# 02_IO.net
KiCad netlist of a schematic drawn in Altium Designer
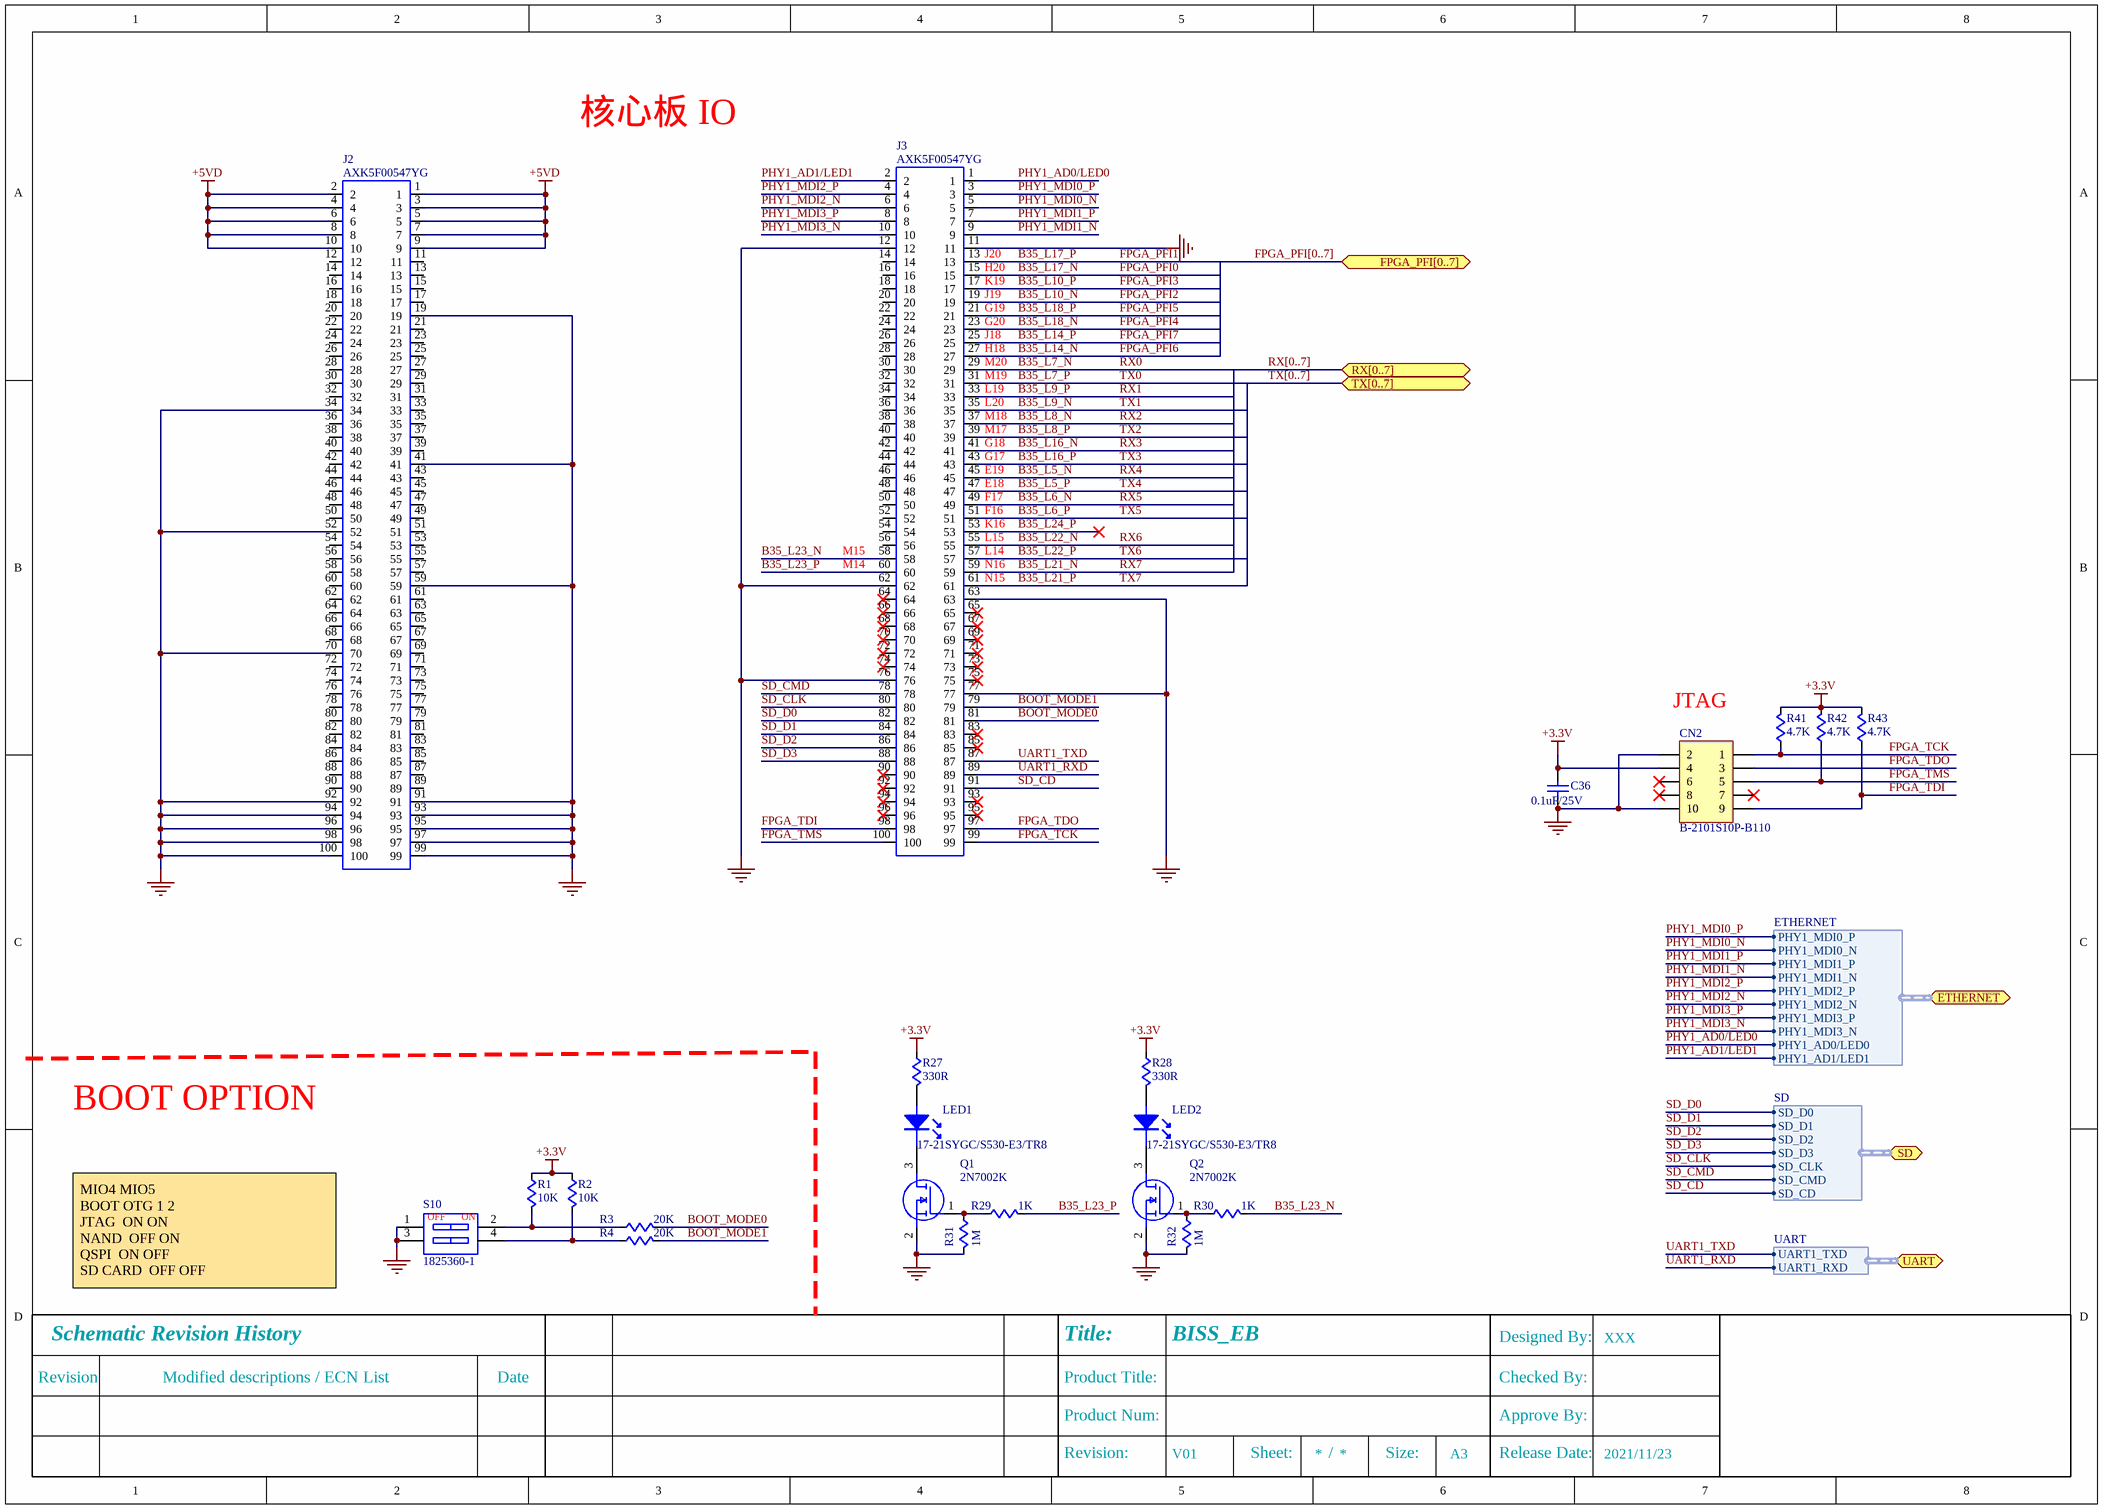
[diagram p0: 02_IO.SchDoc]

(export (version "E")
  (design (tool "Eeschema 10.0.6"))
  (components
    (comp (ref "C36")
      (value "0.1uF/25V")
      (footprint "SamacSys:C0603")
      (description "MLCC")
      (libsource (lib "SamacSys") (part "C"))
    )
    (comp (ref "CN2")
      (value "B-2101S10P-B110")
      (footprint "SHF10501FDTH")
      (description "5*2P接插件,间距1.27mm,参考链接：https://so.szlcsc.com/global.html?k=B-2101S10P-B110&hot-key=LM358")
      (fields (field (name "版权归属") "源创客"))
      (libsource (lib "4.3   - 接插件-脚距1.27") (part "Header 5X2"))
    )
    (comp (ref "J2")
      (value "AXK5F00547YG")
      (footprint "AXK5F00547YG")
      (description "Header_2X50_0.5mm")
      (libsource (lib "*") (part "Header_2X50"))
    )
    (comp (ref "J3")
      (value "AXK5F00547YG")
      (footprint "AXK5F00547YG")
      (description "Header_2X50_0.5mm")
      (libsource (lib "*") (part "Header_2X50"))
    )
    (comp (ref "LED1")
      (value "17-21SYGC/S530-E3/TR8")
      (footprint "LED_0805")
      (libsource (lib "Topband1") (part "LED"))
    )
    (comp (ref "LED2")
      (value "17-21SYGC/S530-E3/TR8")
      (footprint "LED_0805")
      (libsource (lib "Topband1") (part "LED"))
    )
    (comp (ref "Q1")
      (value "2N7002K")
      (footprint "SamacSys:SOT95P240X120-3N")
      (description "MOSFET (N-Channel)")
      (fields (field (name "MOUSER PART NUMBER") "512-2N7002K"))
      (libsource (lib "*") (part "2N7002K"))
    )
    (comp (ref "Q2")
      (value "2N7002K")
      (footprint "SamacSys:SOT95P240X120-3N")
      (description "MOSFET (N-Channel)")
      (fields (field (name "MOUSER PART NUMBER") "512-2N7002K"))
      (libsource (lib "*") (part "2N7002K"))
    )
    (comp (ref "R1")
      (value "10K")
      (footprint "SamacSys:R0603")
      (description "贴片电阻")
      (libsource (lib "SamacSys") (part "R"))
    )
    (comp (ref "R2")
      (value "10K")
      (footprint "SamacSys:R0603")
      (description "贴片电阻")
      (libsource (lib "SamacSys") (part "R"))
    )
    (comp (ref "R3")
      (value "20K")
      (footprint "SamacSys:R0603")
      (description "贴片电阻")
      (libsource (lib "SamacSys") (part "R"))
    )
    (comp (ref "R4")
      (value "20K")
      (footprint "SamacSys:R0603")
      (description "贴片电阻")
      (libsource (lib "SamacSys") (part "R"))
    )
    (comp (ref "R27")
      (value "330R")
      (footprint "SamacSys:R0603")
      (description "贴片电阻")
      (libsource (lib "SamacSys") (part "R"))
    )
    (comp (ref "R28")
      (value "330R")
      (footprint "SamacSys:R0603")
      (description "贴片电阻")
      (libsource (lib "SamacSys") (part "R"))
    )
    (comp (ref "R29")
      (value "1K")
      (footprint "SamacSys:R0603")
      (description "贴片电阻")
      (libsource (lib "SamacSys") (part "R"))
    )
    (comp (ref "R30")
      (value "1K")
      (footprint "SamacSys:R0603")
      (description "贴片电阻")
      (libsource (lib "SamacSys") (part "R"))
    )
    (comp (ref "R31")
      (value "1M")
      (footprint "SamacSys:R0603")
      (description "贴片电阻")
      (libsource (lib "SamacSys") (part "R"))
    )
    (comp (ref "R32")
      (value "1M")
      (footprint "SamacSys:R0603")
      (description "贴片电阻")
      (libsource (lib "SamacSys") (part "R"))
    )
    (comp (ref "R41")
      (value "4.7K")
      (footprint "SamacSys:R0603")
      (description "贴片电阻")
      (libsource (lib "SamacSys") (part "R"))
    )
    (comp (ref "R42")
      (value "4.7K")
      (footprint "SamacSys:R0603")
      (description "贴片电阻")
      (libsource (lib "SamacSys") (part "R"))
    )
    (comp (ref "R43")
      (value "4.7K")
      (footprint "SamacSys:R0603")
      (description "贴片电阻")
      (libsource (lib "SamacSys") (part "R"))
    )
    (comp (ref "S10")
      (value "1825360-1")
      (footprint "SamacSys:18253601")
      (description "Switch")
      (fields (field (name "MOUSER PART NUMBER") "655-1825360-1"))
      (libsource (lib "SamacSys") (part "1825360-1"))
    )
  )
  (nets
    (net (code "4") (name "+3.3V") (class "Default")
      (node (ref "C36") (pin "1") (pinfunction "1_1") (pintype "passive"))
      (node (ref "CN2") (pin "4") (pinfunction "4_4") (pintype "passive"))
      (node (ref "R1") (pin "1") (pinfunction "1_1") (pintype "passive"))
      (node (ref "R2") (pin "1") (pinfunction "1_1") (pintype "passive"))
      (node (ref "R27") (pin "1") (pinfunction "1_1") (pintype "passive"))
      (node (ref "R28") (pin "1") (pinfunction "1_1") (pintype "passive"))
      (node (ref "R41") (pin "2") (pinfunction "2_2") (pintype "passive"))
      (node (ref "R42") (pin "2") (pinfunction "2_2") (pintype "passive"))
      (node (ref "R43") (pin "2") (pinfunction "2_2") (pintype "passive"))
    )
    (net (code "5") (name "+5VD") (class "Default")
      (node (ref "J2") (pin "1") (pinfunction "1_1") (pintype "passive"))
      (node (ref "J2") (pin "10") (pinfunction "10_10") (pintype "passive"))
      (node (ref "J2") (pin "2") (pinfunction "2_2") (pintype "passive"))
      (node (ref "J2") (pin "3") (pinfunction "3_3") (pintype "passive"))
      (node (ref "J2") (pin "4") (pinfunction "4_4") (pintype "passive"))
      (node (ref "J2") (pin "5") (pinfunction "5_5") (pintype "passive"))
      (node (ref "J2") (pin "6") (pinfunction "6_6") (pintype "passive"))
      (node (ref "J2") (pin "7") (pinfunction "7_7") (pintype "passive"))
      (node (ref "J2") (pin "8") (pinfunction "8_8") (pintype "passive"))
      (node (ref "J2") (pin "9") (pinfunction "9_9") (pintype "passive"))
    )
    (net (code "6") (name "/B35_L23_N") (class "Default")
      (node (ref "J3") (pin "58") (pinfunction "58_58") (pintype "passive"))
      (node (ref "R30") (pin "2") (pinfunction "2_2") (pintype "passive"))
    )
    (net (code "7") (name "/B35_L23_P") (class "Default")
      (node (ref "J3") (pin "60") (pinfunction "60_60") (pintype "passive"))
      (node (ref "R29") (pin "2") (pinfunction "2_2") (pintype "passive"))
    )
    (net (code "8") (name "/B35_L24_P") (class "Default")
      (node (ref "J3") (pin "53") (pinfunction "53_53") (pintype "passive+no_connect"))
    )
    (net (code "9") (name "/BOOT_MODE0") (class "Default")
      (node (ref "J3") (pin "81") (pinfunction "81_81") (pintype "passive"))
      (node (ref "R3") (pin "2") (pinfunction "2_2") (pintype "passive"))
    )
    (net (code "10") (name "/BOOT_MODE1") (class "Default")
      (node (ref "J3") (pin "79") (pinfunction "79_79") (pintype "passive"))
      (node (ref "R4") (pin "2") (pinfunction "2_2") (pintype "passive"))
    )
    (net (code "11") (name "/FPGA_PFI0") (class "Default")
      (node (ref "J3") (pin "15") (pinfunction "15_15") (pintype "passive"))
    )
    (net (code "12") (name "/FPGA_PFI1") (class "Default")
      (node (ref "J3") (pin "13") (pinfunction "13_13") (pintype "passive"))
    )
    (net (code "13") (name "/FPGA_PFI2") (class "Default")
      (node (ref "J3") (pin "19") (pinfunction "19_19") (pintype "passive"))
    )
    (net (code "14") (name "/FPGA_PFI3") (class "Default")
      (node (ref "J3") (pin "17") (pinfunction "17_17") (pintype "passive"))
    )
    (net (code "15") (name "/FPGA_PFI4") (class "Default")
      (node (ref "J3") (pin "23") (pinfunction "23_23") (pintype "passive"))
    )
    (net (code "16") (name "/FPGA_PFI5") (class "Default")
      (node (ref "J3") (pin "21") (pinfunction "21_21") (pintype "passive"))
    )
    (net (code "17") (name "/FPGA_PFI6") (class "Default")
      (node (ref "J3") (pin "27") (pinfunction "27_27") (pintype "passive"))
    )
    (net (code "18") (name "/FPGA_PFI7") (class "Default")
      (node (ref "J3") (pin "25") (pinfunction "25_25") (pintype "passive"))
    )
    (net (code "20") (name "/FPGA_TCK") (class "Default")
      (node (ref "CN2") (pin "1") (pinfunction "1_1") (pintype "passive"))
      (node (ref "J3") (pin "99") (pinfunction "99_99") (pintype "passive"))
      (node (ref "R41") (pin "1") (pinfunction "1_1") (pintype "passive"))
    )
    (net (code "21") (name "/FPGA_TDI") (class "Default")
      (node (ref "CN2") (pin "9") (pinfunction "9_9") (pintype "passive"))
      (node (ref "J3") (pin "98") (pinfunction "98_98") (pintype "passive"))
      (node (ref "R43") (pin "1") (pinfunction "1_1") (pintype "passive"))
    )
    (net (code "22") (name "/FPGA_TDO") (class "Default")
      (node (ref "CN2") (pin "3") (pinfunction "3_3") (pintype "passive"))
      (node (ref "J3") (pin "97") (pinfunction "97_97") (pintype "passive"))
    )
    (net (code "23") (name "/FPGA_TMS") (class "Default")
      (node (ref "CN2") (pin "5") (pinfunction "5_5") (pintype "passive"))
      (node (ref "J3") (pin "100") (pinfunction "100_100") (pintype "passive"))
      (node (ref "R42") (pin "1") (pinfunction "1_1") (pintype "passive"))
    )
    (net (code "24") (name "/PHY1_AD0{slash}LED0") (class "Default")
      (node (ref "J3") (pin "1") (pinfunction "1_1") (pintype "passive"))
    )
    (net (code "25") (name "/PHY1_AD1{slash}LED1") (class "Default")
      (node (ref "J3") (pin "2") (pinfunction "2_2") (pintype "passive"))
    )
    (net (code "26") (name "/PHY1_MDI0_N") (class "Default")
      (node (ref "J3") (pin "5") (pinfunction "5_5") (pintype "passive"))
    )
    (net (code "27") (name "/PHY1_MDI0_P") (class "Default")
      (node (ref "J3") (pin "3") (pinfunction "3_3") (pintype "passive"))
    )
    (net (code "28") (name "/PHY1_MDI1_N") (class "Default")
      (node (ref "J3") (pin "9") (pinfunction "9_9") (pintype "passive"))
    )
    (net (code "29") (name "/PHY1_MDI1_P") (class "Default")
      (node (ref "J3") (pin "7") (pinfunction "7_7") (pintype "passive"))
    )
    (net (code "30") (name "/PHY1_MDI2_N") (class "Default")
      (node (ref "J3") (pin "6") (pinfunction "6_6") (pintype "passive"))
    )
    (net (code "31") (name "/PHY1_MDI2_P") (class "Default")
      (node (ref "J3") (pin "4") (pinfunction "4_4") (pintype "passive"))
    )
    (net (code "32") (name "/PHY1_MDI3_N") (class "Default")
      (node (ref "J3") (pin "10") (pinfunction "10_10") (pintype "passive"))
    )
    (net (code "33") (name "/PHY1_MDI3_P") (class "Default")
      (node (ref "J3") (pin "8") (pinfunction "8_8") (pintype "passive"))
    )
    (net (code "34") (name "/RX0") (class "Default")
      (node (ref "J3") (pin "29") (pinfunction "29_29") (pintype "passive"))
    )
    (net (code "35") (name "/RX1") (class "Default")
      (node (ref "J3") (pin "33") (pinfunction "33_33") (pintype "passive"))
    )
    (net (code "36") (name "/RX2") (class "Default")
      (node (ref "J3") (pin "37") (pinfunction "37_37") (pintype "passive"))
    )
    (net (code "37") (name "/RX3") (class "Default")
      (node (ref "J3") (pin "41") (pinfunction "41_41") (pintype "passive"))
    )
    (net (code "38") (name "/RX4") (class "Default")
      (node (ref "J3") (pin "45") (pinfunction "45_45") (pintype "passive"))
    )
    (net (code "39") (name "/RX5") (class "Default")
      (node (ref "J3") (pin "49") (pinfunction "49_49") (pintype "passive"))
    )
    (net (code "40") (name "/RX6") (class "Default")
      (node (ref "J3") (pin "55") (pinfunction "55_55") (pintype "passive"))
    )
    (net (code "41") (name "/RX7") (class "Default")
      (node (ref "J3") (pin "59") (pinfunction "59_59") (pintype "passive"))
    )
    (net (code "43") (name "/SD_CD") (class "Default")
      (node (ref "J3") (pin "91") (pinfunction "91_91") (pintype "passive"))
    )
    (net (code "44") (name "/SD_CLK") (class "Default")
      (node (ref "J3") (pin "80") (pinfunction "80_80") (pintype "passive"))
    )
    (net (code "45") (name "/SD_CMD") (class "Default")
      (node (ref "J3") (pin "78") (pinfunction "78_78") (pintype "passive"))
    )
    (net (code "46") (name "/SD_D0") (class "Default")
      (node (ref "J3") (pin "82") (pinfunction "82_82") (pintype "passive"))
    )
    (net (code "47") (name "/SD_D1") (class "Default")
      (node (ref "J3") (pin "84") (pinfunction "84_84") (pintype "passive"))
    )
    (net (code "48") (name "/SD_D2") (class "Default")
      (node (ref "J3") (pin "86") (pinfunction "86_86") (pintype "passive"))
    )
    (net (code "49") (name "/SD_D3") (class "Default")
      (node (ref "J3") (pin "88") (pinfunction "88_88") (pintype "passive"))
    )
    (net (code "50") (name "/TX0") (class "Default")
      (node (ref "J3") (pin "31") (pinfunction "31_31") (pintype "passive"))
    )
    (net (code "51") (name "/TX1") (class "Default")
      (node (ref "J3") (pin "35") (pinfunction "35_35") (pintype "passive"))
    )
    (net (code "52") (name "/TX2") (class "Default")
      (node (ref "J3") (pin "39") (pinfunction "39_39") (pintype "passive"))
    )
    (net (code "53") (name "/TX3") (class "Default")
      (node (ref "J3") (pin "43") (pinfunction "43_43") (pintype "passive"))
    )
    (net (code "54") (name "/TX4") (class "Default")
      (node (ref "J3") (pin "47") (pinfunction "47_47") (pintype "passive"))
    )
    (net (code "55") (name "/TX5") (class "Default")
      (node (ref "J3") (pin "51") (pinfunction "51_51") (pintype "passive"))
    )
    (net (code "56") (name "/TX6") (class "Default")
      (node (ref "J3") (pin "57") (pinfunction "57_57") (pintype "passive"))
    )
    (net (code "57") (name "/TX7") (class "Default")
      (node (ref "J3") (pin "61") (pinfunction "61_61") (pintype "passive"))
    )
    (net (code "59") (name "/UART1_RXD") (class "Default")
      (node (ref "J3") (pin "89") (pinfunction "89_89") (pintype "passive"))
    )
    (net (code "60") (name "/UART1_TXD") (class "Default")
      (node (ref "J3") (pin "87") (pinfunction "87_87") (pintype "passive"))
    )
    (net (code "64") (name "GND") (class "Default")
      (node (ref "C36") (pin "2") (pinfunction "2_2") (pintype "passive"))
      (node (ref "CN2") (pin "10") (pinfunction "10_10") (pintype "passive"))
      (node (ref "CN2") (pin "2") (pinfunction "2_2") (pintype "passive"))
      (node (ref "J2") (pin "100") (pinfunction "100_100") (pintype "passive"))
      (node (ref "J2") (pin "19") (pinfunction "19_19") (pintype "passive"))
      (node (ref "J2") (pin "34") (pinfunction "34_34") (pintype "passive"))
      (node (ref "J2") (pin "41") (pinfunction "41_41") (pintype "passive"))
      (node (ref "J2") (pin "52") (pinfunction "52_52") (pintype "passive"))
      (node (ref "J2") (pin "59") (pinfunction "59_59") (pintype "passive"))
      (node (ref "J2") (pin "70") (pinfunction "70_70") (pintype "passive"))
      (node (ref "J2") (pin "91") (pinfunction "91_91") (pintype "passive"))
      (node (ref "J2") (pin "92") (pinfunction "92_92") (pintype "passive"))
      (node (ref "J2") (pin "93") (pinfunction "93_93") (pintype "passive"))
      (node (ref "J2") (pin "94") (pinfunction "94_94") (pintype "passive"))
      (node (ref "J2") (pin "95") (pinfunction "95_95") (pintype "passive"))
      (node (ref "J2") (pin "96") (pinfunction "96_96") (pintype "passive"))
      (node (ref "J2") (pin "97") (pinfunction "97_97") (pintype "passive"))
      (node (ref "J2") (pin "98") (pinfunction "98_98") (pintype "passive"))
      (node (ref "J2") (pin "99") (pinfunction "99_99") (pintype "passive"))
      (node (ref "J3") (pin "11") (pinfunction "11_11") (pintype "passive"))
      (node (ref "J3") (pin "12") (pinfunction "12_12") (pintype "passive"))
      (node (ref "J3") (pin "62") (pinfunction "62_62") (pintype "passive"))
      (node (ref "J3") (pin "63") (pinfunction "63_63") (pintype "passive"))
      (node (ref "J3") (pin "76") (pinfunction "76_76") (pintype "passive"))
      (node (ref "J3") (pin "77") (pinfunction "77_77") (pintype "passive"))
      (node (ref "Q1") (pin "2") (pinfunction "S_2") (pintype "passive"))
      (node (ref "Q2") (pin "2") (pinfunction "S_2") (pintype "passive"))
      (node (ref "R31") (pin "2") (pinfunction "2_2") (pintype "passive"))
      (node (ref "R32") (pin "2") (pinfunction "2_2") (pintype "passive"))
      (node (ref "S10") (pin "1") (pinfunction "1_1") (pintype "passive"))
      (node (ref "S10") (pin "3") (pinfunction "3_3") (pintype "passive"))
    )
    (net (code "65") (name "Net-(LED1-PadA)") (class "Default")
      (node (ref "LED1") (pin "A") (pinfunction "A_A") (pintype "passive"))
      (node (ref "R27") (pin "2") (pinfunction "2_2") (pintype "passive"))
    )
    (net (code "66") (name "Net-(LED2-PadA)") (class "Default")
      (node (ref "LED2") (pin "A") (pinfunction "A_A") (pintype "passive"))
      (node (ref "R28") (pin "2") (pinfunction "2_2") (pintype "passive"))
    )
    (net (code "67") (name "Net-(Q1-D)") (class "Default")
      (node (ref "LED1") (pin "K") (pinfunction "K_K") (pintype "passive"))
      (node (ref "Q1") (pin "3") (pinfunction "D_3") (pintype "passive"))
    )
    (net (code "68") (name "Net-(Q1-G)") (class "Default")
      (node (ref "Q1") (pin "1") (pinfunction "G_1") (pintype "passive"))
      (node (ref "R29") (pin "1") (pinfunction "1_1") (pintype "passive"))
      (node (ref "R31") (pin "1") (pinfunction "1_1") (pintype "passive"))
    )
    (net (code "69") (name "Net-(Q2-D)") (class "Default")
      (node (ref "LED2") (pin "K") (pinfunction "K_K") (pintype "passive"))
      (node (ref "Q2") (pin "3") (pinfunction "D_3") (pintype "passive"))
    )
    (net (code "70") (name "Net-(Q2-G)") (class "Default")
      (node (ref "Q2") (pin "1") (pinfunction "G_1") (pintype "passive"))
      (node (ref "R30") (pin "1") (pinfunction "1_1") (pintype "passive"))
      (node (ref "R32") (pin "1") (pinfunction "1_1") (pintype "passive"))
    )
    (net (code "71") (name "Net-(R1-Pad2)") (class "Default")
      (node (ref "R1") (pin "2") (pinfunction "2_2") (pintype "passive"))
      (node (ref "R3") (pin "1") (pinfunction "1_1") (pintype "passive"))
      (node (ref "S10") (pin "2") (pinfunction "2_2") (pintype "passive"))
    )
    (net (code "72") (name "Net-(R2-Pad2)") (class "Default")
      (node (ref "R2") (pin "2") (pinfunction "2_2") (pintype "passive"))
      (node (ref "R4") (pin "1") (pinfunction "1_1") (pintype "passive"))
      (node (ref "S10") (pin "4") (pinfunction "4_4") (pintype "passive"))
    )
    (net (code "73") (name "unconnected-(CN2-Pad6)") (class "Default")
      (node (ref "CN2") (pin "6") (pinfunction "6_6") (pintype "passive+no_connect"))
    )
    (net (code "74") (name "unconnected-(CN2-Pad7)") (class "Default")
      (node (ref "CN2") (pin "7") (pinfunction "7_7") (pintype "passive+no_connect"))
    )
    (net (code "75") (name "unconnected-(CN2-Pad8)") (class "Default")
      (node (ref "CN2") (pin "8") (pinfunction "8_8") (pintype "passive+no_connect"))
    )
    (net (code "76") (name "unconnected-(J2-Pad11)") (class "Default")
      (node (ref "J2") (pin "11") (pinfunction "11_11") (pintype "passive"))
    )
    (net (code "77") (name "unconnected-(J2-Pad12)") (class "Default")
      (node (ref "J2") (pin "12") (pinfunction "12_12") (pintype "passive"))
    )
    (net (code "78") (name "unconnected-(J2-Pad13)") (class "Default")
      (node (ref "J2") (pin "13") (pinfunction "13_13") (pintype "passive"))
    )
    (net (code "79") (name "unconnected-(J2-Pad14)") (class "Default")
      (node (ref "J2") (pin "14") (pinfunction "14_14") (pintype "passive"))
    )
    (net (code "80") (name "unconnected-(J2-Pad15)") (class "Default")
      (node (ref "J2") (pin "15") (pinfunction "15_15") (pintype "passive"))
    )
    (net (code "81") (name "unconnected-(J2-Pad16)") (class "Default")
      (node (ref "J2") (pin "16") (pinfunction "16_16") (pintype "passive"))
    )
    (net (code "82") (name "unconnected-(J2-Pad17)") (class "Default")
      (node (ref "J2") (pin "17") (pinfunction "17_17") (pintype "passive"))
    )
    (net (code "83") (name "unconnected-(J2-Pad18)") (class "Default")
      (node (ref "J2") (pin "18") (pinfunction "18_18") (pintype "passive"))
    )
    (net (code "84") (name "unconnected-(J2-Pad20)") (class "Default")
      (node (ref "J2") (pin "20") (pinfunction "20_20") (pintype "passive"))
    )
    (net (code "85") (name "unconnected-(J2-Pad21)") (class "Default")
      (node (ref "J2") (pin "21") (pinfunction "21_21") (pintype "passive"))
    )
    (net (code "86") (name "unconnected-(J2-Pad22)") (class "Default")
      (node (ref "J2") (pin "22") (pinfunction "22_22") (pintype "passive"))
    )
    (net (code "87") (name "unconnected-(J2-Pad23)") (class "Default")
      (node (ref "J2") (pin "23") (pinfunction "23_23") (pintype "passive"))
    )
    (net (code "88") (name "unconnected-(J2-Pad24)") (class "Default")
      (node (ref "J2") (pin "24") (pinfunction "24_24") (pintype "passive"))
    )
    (net (code "89") (name "unconnected-(J2-Pad25)") (class "Default")
      (node (ref "J2") (pin "25") (pinfunction "25_25") (pintype "passive"))
    )
    (net (code "90") (name "unconnected-(J2-Pad26)") (class "Default")
      (node (ref "J2") (pin "26") (pinfunction "26_26") (pintype "passive"))
    )
    (net (code "91") (name "unconnected-(J2-Pad27)") (class "Default")
      (node (ref "J2") (pin "27") (pinfunction "27_27") (pintype "passive"))
    )
    (net (code "92") (name "unconnected-(J2-Pad28)") (class "Default")
      (node (ref "J2") (pin "28") (pinfunction "28_28") (pintype "passive"))
    )
    (net (code "93") (name "unconnected-(J2-Pad29)") (class "Default")
      (node (ref "J2") (pin "29") (pinfunction "29_29") (pintype "passive"))
    )
    (net (code "94") (name "unconnected-(J2-Pad30)") (class "Default")
      (node (ref "J2") (pin "30") (pinfunction "30_30") (pintype "passive"))
    )
    (net (code "95") (name "unconnected-(J2-Pad31)") (class "Default")
      (node (ref "J2") (pin "31") (pinfunction "31_31") (pintype "passive"))
    )
    (net (code "96") (name "unconnected-(J2-Pad32)") (class "Default")
      (node (ref "J2") (pin "32") (pinfunction "32_32") (pintype "passive"))
    )
    (net (code "97") (name "unconnected-(J2-Pad33)") (class "Default")
      (node (ref "J2") (pin "33") (pinfunction "33_33") (pintype "passive"))
    )
    (net (code "98") (name "unconnected-(J2-Pad35)") (class "Default")
      (node (ref "J2") (pin "35") (pinfunction "35_35") (pintype "passive"))
    )
    (net (code "99") (name "unconnected-(J2-Pad36)") (class "Default")
      (node (ref "J2") (pin "36") (pinfunction "36_36") (pintype "passive"))
    )
    (net (code "100") (name "unconnected-(J2-Pad37)") (class "Default")
      (node (ref "J2") (pin "37") (pinfunction "37_37") (pintype "passive"))
    )
    (net (code "101") (name "unconnected-(J2-Pad38)") (class "Default")
      (node (ref "J2") (pin "38") (pinfunction "38_38") (pintype "passive"))
    )
    (net (code "102") (name "unconnected-(J2-Pad39)") (class "Default")
      (node (ref "J2") (pin "39") (pinfunction "39_39") (pintype "passive"))
    )
    (net (code "103") (name "unconnected-(J2-Pad40)") (class "Default")
      (node (ref "J2") (pin "40") (pinfunction "40_40") (pintype "passive"))
    )
    (net (code "104") (name "unconnected-(J2-Pad42)") (class "Default")
      (node (ref "J2") (pin "42") (pinfunction "42_42") (pintype "passive"))
    )
    (net (code "105") (name "unconnected-(J2-Pad43)") (class "Default")
      (node (ref "J2") (pin "43") (pinfunction "43_43") (pintype "passive"))
    )
    (net (code "106") (name "unconnected-(J2-Pad44)") (class "Default")
      (node (ref "J2") (pin "44") (pinfunction "44_44") (pintype "passive"))
    )
    (net (code "107") (name "unconnected-(J2-Pad45)") (class "Default")
      (node (ref "J2") (pin "45") (pinfunction "45_45") (pintype "passive"))
    )
    (net (code "108") (name "unconnected-(J2-Pad46)") (class "Default")
      (node (ref "J2") (pin "46") (pinfunction "46_46") (pintype "passive"))
    )
    (net (code "109") (name "unconnected-(J2-Pad47)") (class "Default")
      (node (ref "J2") (pin "47") (pinfunction "47_47") (pintype "passive"))
    )
    (net (code "110") (name "unconnected-(J2-Pad48)") (class "Default")
      (node (ref "J2") (pin "48") (pinfunction "48_48") (pintype "passive"))
    )
    (net (code "111") (name "unconnected-(J2-Pad49)") (class "Default")
      (node (ref "J2") (pin "49") (pinfunction "49_49") (pintype "passive"))
    )
    (net (code "112") (name "unconnected-(J2-Pad50)") (class "Default")
      (node (ref "J2") (pin "50") (pinfunction "50_50") (pintype "passive"))
    )
    (net (code "113") (name "unconnected-(J2-Pad51)") (class "Default")
      (node (ref "J2") (pin "51") (pinfunction "51_51") (pintype "passive"))
    )
    (net (code "114") (name "unconnected-(J2-Pad53)") (class "Default")
      (node (ref "J2") (pin "53") (pinfunction "53_53") (pintype "passive"))
    )
    (net (code "115") (name "unconnected-(J2-Pad54)") (class "Default")
      (node (ref "J2") (pin "54") (pinfunction "54_54") (pintype "passive"))
    )
    (net (code "116") (name "unconnected-(J2-Pad55)") (class "Default")
      (node (ref "J2") (pin "55") (pinfunction "55_55") (pintype "passive"))
    )
    (net (code "117") (name "unconnected-(J2-Pad56)") (class "Default")
      (node (ref "J2") (pin "56") (pinfunction "56_56") (pintype "passive"))
    )
    (net (code "118") (name "unconnected-(J2-Pad57)") (class "Default")
      (node (ref "J2") (pin "57") (pinfunction "57_57") (pintype "passive"))
    )
    (net (code "119") (name "unconnected-(J2-Pad58)") (class "Default")
      (node (ref "J2") (pin "58") (pinfunction "58_58") (pintype "passive"))
    )
    (net (code "120") (name "unconnected-(J2-Pad60)") (class "Default")
      (node (ref "J2") (pin "60") (pinfunction "60_60") (pintype "passive"))
    )
    (net (code "121") (name "unconnected-(J2-Pad61)") (class "Default")
      (node (ref "J2") (pin "61") (pinfunction "61_61") (pintype "passive"))
    )
    (net (code "122") (name "unconnected-(J2-Pad62)") (class "Default")
      (node (ref "J2") (pin "62") (pinfunction "62_62") (pintype "passive"))
    )
    (net (code "123") (name "unconnected-(J2-Pad63)") (class "Default")
      (node (ref "J2") (pin "63") (pinfunction "63_63") (pintype "passive"))
    )
    (net (code "124") (name "unconnected-(J2-Pad64)") (class "Default")
      (node (ref "J2") (pin "64") (pinfunction "64_64") (pintype "passive"))
    )
    (net (code "125") (name "unconnected-(J2-Pad65)") (class "Default")
      (node (ref "J2") (pin "65") (pinfunction "65_65") (pintype "passive"))
    )
    (net (code "126") (name "unconnected-(J2-Pad66)") (class "Default")
      (node (ref "J2") (pin "66") (pinfunction "66_66") (pintype "passive"))
    )
    (net (code "127") (name "unconnected-(J2-Pad67)") (class "Default")
      (node (ref "J2") (pin "67") (pinfunction "67_67") (pintype "passive"))
    )
    (net (code "128") (name "unconnected-(J2-Pad68)") (class "Default")
      (node (ref "J2") (pin "68") (pinfunction "68_68") (pintype "passive"))
    )
    (net (code "129") (name "unconnected-(J2-Pad69)") (class "Default")
      (node (ref "J2") (pin "69") (pinfunction "69_69") (pintype "passive"))
    )
    (net (code "130") (name "unconnected-(J2-Pad71)") (class "Default")
      (node (ref "J2") (pin "71") (pinfunction "71_71") (pintype "passive"))
    )
    (net (code "131") (name "unconnected-(J2-Pad72)") (class "Default")
      (node (ref "J2") (pin "72") (pinfunction "72_72") (pintype "passive"))
    )
    (net (code "132") (name "unconnected-(J2-Pad73)") (class "Default")
      (node (ref "J2") (pin "73") (pinfunction "73_73") (pintype "passive"))
    )
    (net (code "133") (name "unconnected-(J2-Pad74)") (class "Default")
      (node (ref "J2") (pin "74") (pinfunction "74_74") (pintype "passive"))
    )
    (net (code "134") (name "unconnected-(J2-Pad75)") (class "Default")
      (node (ref "J2") (pin "75") (pinfunction "75_75") (pintype "passive"))
    )
    (net (code "135") (name "unconnected-(J2-Pad76)") (class "Default")
      (node (ref "J2") (pin "76") (pinfunction "76_76") (pintype "passive"))
    )
    (net (code "136") (name "unconnected-(J2-Pad77)") (class "Default")
      (node (ref "J2") (pin "77") (pinfunction "77_77") (pintype "passive"))
    )
    (net (code "137") (name "unconnected-(J2-Pad78)") (class "Default")
      (node (ref "J2") (pin "78") (pinfunction "78_78") (pintype "passive"))
    )
    (net (code "138") (name "unconnected-(J2-Pad79)") (class "Default")
      (node (ref "J2") (pin "79") (pinfunction "79_79") (pintype "passive"))
    )
    (net (code "139") (name "unconnected-(J2-Pad80)") (class "Default")
      (node (ref "J2") (pin "80") (pinfunction "80_80") (pintype "passive"))
    )
    (net (code "140") (name "unconnected-(J2-Pad81)") (class "Default")
      (node (ref "J2") (pin "81") (pinfunction "81_81") (pintype "passive"))
    )
    (net (code "141") (name "unconnected-(J2-Pad82)") (class "Default")
      (node (ref "J2") (pin "82") (pinfunction "82_82") (pintype "passive"))
    )
    (net (code "142") (name "unconnected-(J2-Pad83)") (class "Default")
      (node (ref "J2") (pin "83") (pinfunction "83_83") (pintype "passive"))
    )
    (net (code "143") (name "unconnected-(J2-Pad84)") (class "Default")
      (node (ref "J2") (pin "84") (pinfunction "84_84") (pintype "passive"))
    )
    (net (code "144") (name "unconnected-(J2-Pad85)") (class "Default")
      (node (ref "J2") (pin "85") (pinfunction "85_85") (pintype "passive"))
    )
    (net (code "145") (name "unconnected-(J2-Pad86)") (class "Default")
      (node (ref "J2") (pin "86") (pinfunction "86_86") (pintype "passive"))
    )
    (net (code "146") (name "unconnected-(J2-Pad87)") (class "Default")
      (node (ref "J2") (pin "87") (pinfunction "87_87") (pintype "passive"))
    )
    (net (code "147") (name "unconnected-(J2-Pad88)") (class "Default")
      (node (ref "J2") (pin "88") (pinfunction "88_88") (pintype "passive"))
    )
    (net (code "148") (name "unconnected-(J2-Pad89)") (class "Default")
      (node (ref "J2") (pin "89") (pinfunction "89_89") (pintype "passive"))
    )
    (net (code "149") (name "unconnected-(J2-Pad90)") (class "Default")
      (node (ref "J2") (pin "90") (pinfunction "90_90") (pintype "passive"))
    )
    (net (code "150") (name "unconnected-(J3-Pad14)") (class "Default")
      (node (ref "J3") (pin "14") (pinfunction "14_14") (pintype "passive"))
    )
    (net (code "151") (name "unconnected-(J3-Pad16)") (class "Default")
      (node (ref "J3") (pin "16") (pinfunction "16_16") (pintype "passive"))
    )
    (net (code "152") (name "unconnected-(J3-Pad18)") (class "Default")
      (node (ref "J3") (pin "18") (pinfunction "18_18") (pintype "passive"))
    )
    (net (code "153") (name "unconnected-(J3-Pad20)") (class "Default")
      (node (ref "J3") (pin "20") (pinfunction "20_20") (pintype "passive"))
    )
    (net (code "154") (name "unconnected-(J3-Pad22)") (class "Default")
      (node (ref "J3") (pin "22") (pinfunction "22_22") (pintype "passive"))
    )
    (net (code "155") (name "unconnected-(J3-Pad24)") (class "Default")
      (node (ref "J3") (pin "24") (pinfunction "24_24") (pintype "passive"))
    )
    (net (code "156") (name "unconnected-(J3-Pad26)") (class "Default")
      (node (ref "J3") (pin "26") (pinfunction "26_26") (pintype "passive"))
    )
    (net (code "157") (name "unconnected-(J3-Pad28)") (class "Default")
      (node (ref "J3") (pin "28") (pinfunction "28_28") (pintype "passive"))
    )
    (net (code "158") (name "unconnected-(J3-Pad30)") (class "Default")
      (node (ref "J3") (pin "30") (pinfunction "30_30") (pintype "passive"))
    )
    (net (code "159") (name "unconnected-(J3-Pad32)") (class "Default")
      (node (ref "J3") (pin "32") (pinfunction "32_32") (pintype "passive"))
    )
    (net (code "160") (name "unconnected-(J3-Pad34)") (class "Default")
      (node (ref "J3") (pin "34") (pinfunction "34_34") (pintype "passive"))
    )
    (net (code "161") (name "unconnected-(J3-Pad36)") (class "Default")
      (node (ref "J3") (pin "36") (pinfunction "36_36") (pintype "passive"))
    )
    (net (code "162") (name "unconnected-(J3-Pad38)") (class "Default")
      (node (ref "J3") (pin "38") (pinfunction "38_38") (pintype "passive"))
    )
    (net (code "163") (name "unconnected-(J3-Pad40)") (class "Default")
      (node (ref "J3") (pin "40") (pinfunction "40_40") (pintype "passive"))
    )
    (net (code "164") (name "unconnected-(J3-Pad42)") (class "Default")
      (node (ref "J3") (pin "42") (pinfunction "42_42") (pintype "passive"))
    )
    (net (code "165") (name "unconnected-(J3-Pad44)") (class "Default")
      (node (ref "J3") (pin "44") (pinfunction "44_44") (pintype "passive"))
    )
    (net (code "166") (name "unconnected-(J3-Pad46)") (class "Default")
      (node (ref "J3") (pin "46") (pinfunction "46_46") (pintype "passive"))
    )
    (net (code "167") (name "unconnected-(J3-Pad48)") (class "Default")
      (node (ref "J3") (pin "48") (pinfunction "48_48") (pintype "passive"))
    )
    (net (code "168") (name "unconnected-(J3-Pad50)") (class "Default")
      (node (ref "J3") (pin "50") (pinfunction "50_50") (pintype "passive"))
    )
    (net (code "169") (name "unconnected-(J3-Pad52)") (class "Default")
      (node (ref "J3") (pin "52") (pinfunction "52_52") (pintype "passive"))
    )
    (net (code "170") (name "unconnected-(J3-Pad54)") (class "Default")
      (node (ref "J3") (pin "54") (pinfunction "54_54") (pintype "passive"))
    )
    (net (code "171") (name "unconnected-(J3-Pad56)") (class "Default")
      (node (ref "J3") (pin "56") (pinfunction "56_56") (pintype "passive"))
    )
    (net (code "172") (name "unconnected-(J3-Pad64)") (class "Default")
      (node (ref "J3") (pin "64") (pinfunction "64_64") (pintype "passive+no_connect"))
    )
    (net (code "173") (name "unconnected-(J3-Pad65)") (class "Default")
      (node (ref "J3") (pin "65") (pinfunction "65_65") (pintype "passive+no_connect"))
    )
    (net (code "174") (name "unconnected-(J3-Pad66)") (class "Default")
      (node (ref "J3") (pin "66") (pinfunction "66_66") (pintype "passive+no_connect"))
    )
    (net (code "175") (name "unconnected-(J3-Pad67)") (class "Default")
      (node (ref "J3") (pin "67") (pinfunction "67_67") (pintype "passive+no_connect"))
    )
    (net (code "176") (name "unconnected-(J3-Pad68)") (class "Default")
      (node (ref "J3") (pin "68") (pinfunction "68_68") (pintype "passive+no_connect"))
    )
    (net (code "177") (name "unconnected-(J3-Pad69)") (class "Default")
      (node (ref "J3") (pin "69") (pinfunction "69_69") (pintype "passive+no_connect"))
    )
    (net (code "178") (name "unconnected-(J3-Pad70)") (class "Default")
      (node (ref "J3") (pin "70") (pinfunction "70_70") (pintype "passive+no_connect"))
    )
    (net (code "179") (name "unconnected-(J3-Pad71)") (class "Default")
      (node (ref "J3") (pin "71") (pinfunction "71_71") (pintype "passive+no_connect"))
    )
    (net (code "180") (name "unconnected-(J3-Pad72)") (class "Default")
      (node (ref "J3") (pin "72") (pinfunction "72_72") (pintype "passive+no_connect"))
    )
    (net (code "181") (name "unconnected-(J3-Pad73)") (class "Default")
      (node (ref "J3") (pin "73") (pinfunction "73_73") (pintype "passive+no_connect"))
    )
    (net (code "182") (name "unconnected-(J3-Pad74)") (class "Default")
      (node (ref "J3") (pin "74") (pinfunction "74_74") (pintype "passive+no_connect"))
    )
    (net (code "183") (name "unconnected-(J3-Pad75)") (class "Default")
      (node (ref "J3") (pin "75") (pinfunction "75_75") (pintype "passive+no_connect"))
    )
    (net (code "184") (name "unconnected-(J3-Pad83)") (class "Default")
      (node (ref "J3") (pin "83") (pinfunction "83_83") (pintype "passive+no_connect"))
    )
    (net (code "185") (name "unconnected-(J3-Pad85)") (class "Default")
      (node (ref "J3") (pin "85") (pinfunction "85_85") (pintype "passive+no_connect"))
    )
    (net (code "186") (name "unconnected-(J3-Pad90)") (class "Default")
      (node (ref "J3") (pin "90") (pinfunction "90_90") (pintype "passive+no_connect"))
    )
    (net (code "187") (name "unconnected-(J3-Pad92)") (class "Default")
      (node (ref "J3") (pin "92") (pinfunction "92_92") (pintype "passive+no_connect"))
    )
    (net (code "188") (name "unconnected-(J3-Pad93)") (class "Default")
      (node (ref "J3") (pin "93") (pinfunction "93_93") (pintype "passive+no_connect"))
    )
    (net (code "189") (name "unconnected-(J3-Pad94)") (class "Default")
      (node (ref "J3") (pin "94") (pinfunction "94_94") (pintype "passive+no_connect"))
    )
    (net (code "190") (name "unconnected-(J3-Pad95)") (class "Default")
      (node (ref "J3") (pin "95") (pinfunction "95_95") (pintype "passive+no_connect"))
    )
    (net (code "191") (name "unconnected-(J3-Pad96)") (class "Default")
      (node (ref "J3") (pin "96") (pinfunction "96_96") (pintype "passive+no_connect"))
    )
  )
)
